# Sheet1.net
KiCad netlist of a schematic drawn in Altium Designer
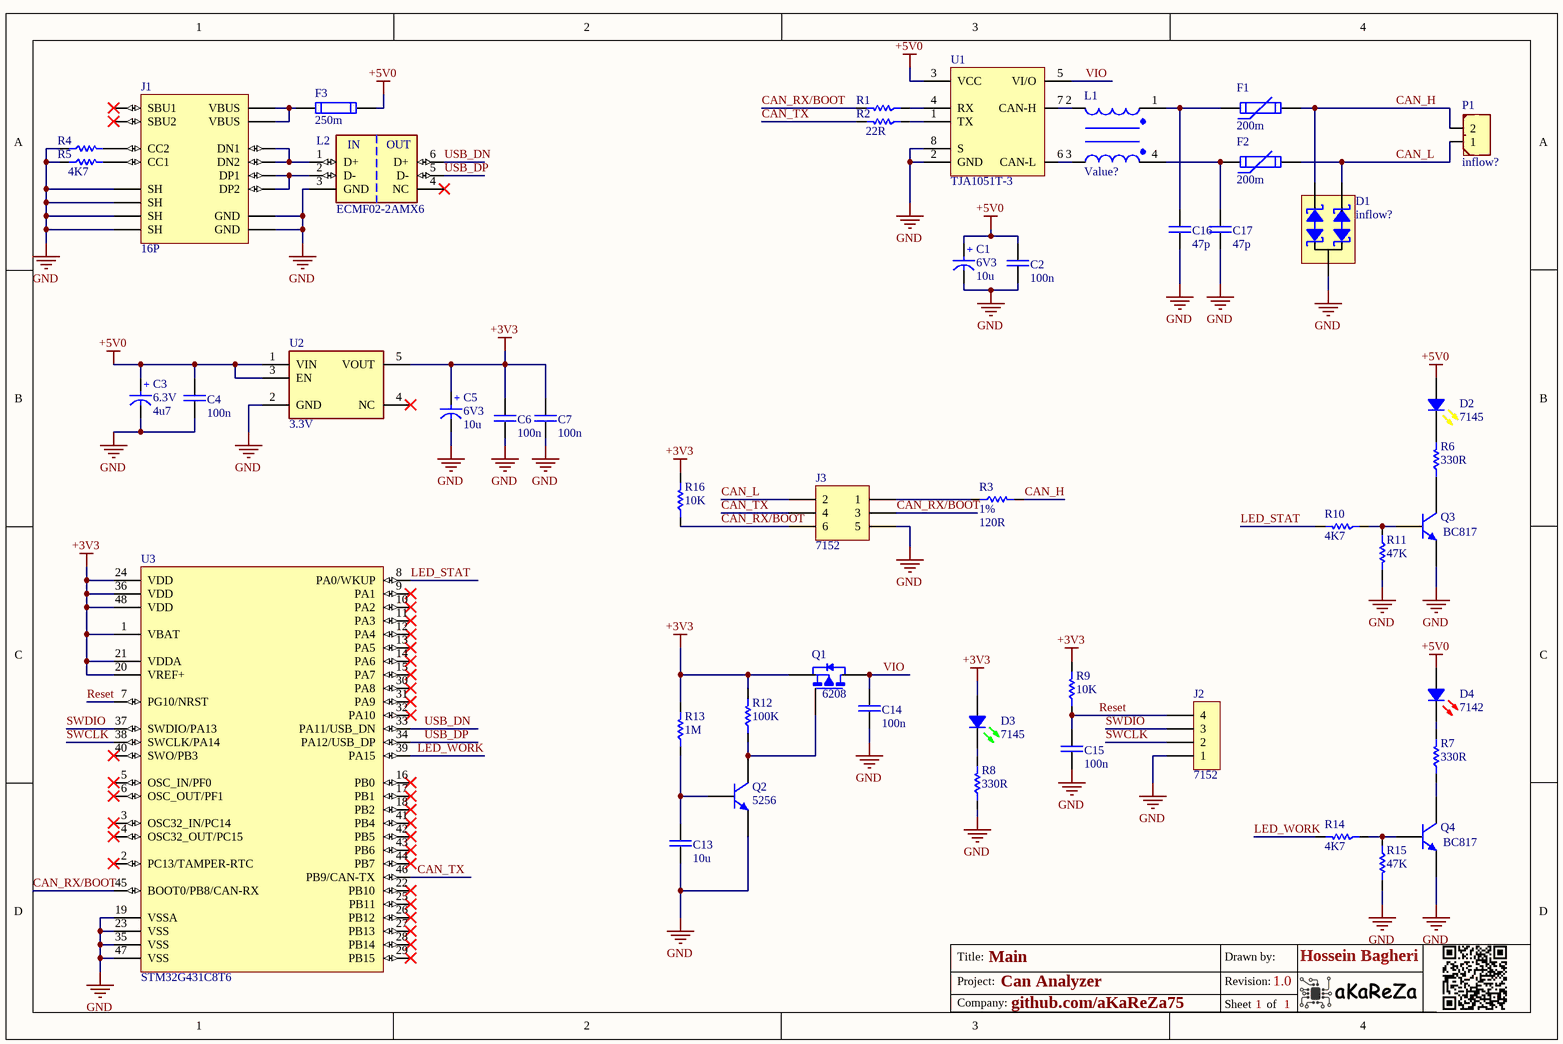
[diagram p0: Sheet1.SchDoc]

(export (version "E")
  (design (tool "Eeschema 10.0.6"))
  (components
    (comp (ref "C1")
      (value "10u")
      (footprint "SMT_C_Tantalum_A")
      (description "Tantalum Capacitor,TAJ Series-SMD")
      (fields (field (name "RATING") "6V3") (field (name "VALIDATION") "Valid"))
      (libsource (lib "aKaReZa") (part "Cap_Tantalum"))
    )
    (comp (ref "C2")
      (value "100n")
      (footprint "CAP 0805/2012")
      (description "Bipolar ceramic capacitor SMD")
      (fields (field (name "VALIDATION") "Valid"))
      (libsource (lib "aKaReZa") (part "Cap_Multi_SMD_100nF_0805"))
    )
    (comp (ref "C3")
      (value "4u7")
      (footprint "SMT_C_Tantalum_A")
      (description "Tantalum Capacitor,TAJ Series-SMD")
      (fields (field (name "RATING") "6.3V"))
      (libsource (lib "aKaReZa") (part "Cap_Tantalum"))
    )
    (comp (ref "C4")
      (value "100n")
      (footprint "CAP 0805/2012")
      (description "Bipolar ceramic capacitor SMD")
      (libsource (lib "aKaReZa") (part "Cap_Multi_SMD_100nF_0805"))
    )
    (comp (ref "C5")
      (value "10u")
      (footprint "SMT_C_Tantalum_B")
      (description "Tantalum Capacitor,TAJ Series-SMD")
      (fields (field (name "RATING") "6V3") (field (name "VALIDATION") "Valid"))
      (libsource (lib "aKaReZa") (part "Cap_Tantalum"))
    )
    (comp (ref "C6")
      (value "100n")
      (footprint "CAP 0805/2012")
      (description "Bipolar ceramic capacitor SMD")
      (fields (field (name "VALIDATION") "Valid"))
      (libsource (lib "aKaReZa") (part "Cap_Multi_SMD_100nF_0805"))
    )
    (comp (ref "C7")
      (value "100n")
      (footprint "CAP 0805/2012")
      (description "Bipolar ceramic capacitor SMD")
      (fields (field (name "VALIDATION") "Valid"))
      (libsource (lib "aKaReZa") (part "Cap_Multi_SMD_100nF_0805"))
    )
    (comp (ref "C13")
      (value "10u")
      (footprint "CAP 0805/2012")
      (description "Bipolar ceramic capacitor SMD")
      (fields (field (name "VALIDATION") "Valid"))
      (libsource (lib "aKaReZa") (part "Cap_Multi_SMD_0805"))
    )
    (comp (ref "C14")
      (value "100n")
      (footprint "CAP 0805/2012")
      (description "Bipolar ceramic capacitor SMD")
      (fields (field (name "VALIDATION") "Valid"))
      (libsource (lib "aKaReZa") (part "Cap_Multi_SMD_100nF_0805"))
    )
    (comp (ref "C15")
      (value "100n")
      (footprint "CAP 0805/2012")
      (description "Bipolar ceramic capacitor SMD")
      (fields (field (name "VALIDATION") "Valid"))
      (libsource (lib "aKaReZa") (part "Cap_Multi_SMD_100nF_0805"))
    )
    (comp (ref "C16")
      (value "47p")
      (footprint "CAP 0805/2012")
      (description "Bipolar ceramic capacitor SMD")
      (fields (field (name "VALIDATION") "Valid"))
      (libsource (lib "aKaReZa") (part "Cap_Multi_SMD_0805"))
    )
    (comp (ref "C17")
      (value "47p")
      (footprint "CAP 0805/2012")
      (description "Bipolar ceramic capacitor SMD")
      (fields (field (name "VALIDATION") "Valid"))
      (libsource (lib "aKaReZa") (part "Cap_Multi_SMD_0805"))
    )
    (comp (ref "D1")
      (value "SM712")
      (footprint "SOT23_M")
      (description "TVS, ESD PROTECT, 2CH, 400W/17A PP, 7.5VBR, ±8KV ESDmin")
      (fields (field (name "INFLOW") "inflow?") (field (name "VALIDATION") "Valid"))
      (libsource (lib "aKaReZa") (part "Semi_Diod_TVS_SM712"))
    )
    (comp (ref "D2")
      (value "Yellow")
      (footprint "LED-3mm_Yellow")
      (description "LED")
      (fields (field (name "INFLOW") "7145") (field (name "VALIDATION") "Valid"))
      (libsource (lib "aKaReZa") (part "Semi_LED_Yellow_3"))
    )
    (comp (ref "D3")
      (value "Green, 3'mm")
      (footprint "led-3mm")
      (description "LED")
      (fields (field (name "INFLOW") "7145") (field (name "VALIDATION") "Valid"))
      (libsource (lib "aKaReZa") (part "Semi_LED_Green_3"))
    )
    (comp (ref "D4")
      (value "Red, 3'mm")
      (footprint "LED-3mm(RED)")
      (description "LED")
      (fields (field (name "INFLOW") "7142") (field (name "VALIDATION") "Valid"))
      (libsource (lib "aKaReZa") (part "Semi_LED_Red_3"))
    )
    (comp (ref "F1")
      (value "200m")
      (footprint "1206_F")
      (description "SMD Resettable Fuses")
      (fields (field (name "VALIDATION") "Valid"))
      (libsource (lib "aKaReZa") (part "Other_Elec_PFUSE_SMD"))
    )
    (comp (ref "F2")
      (value "200m")
      (footprint "1206_F")
      (description "SMD Resettable Fuses")
      (fields (field (name "VALIDATION") "Valid"))
      (libsource (lib "aKaReZa") (part "Other_Elec_PFUSE_SMD"))
    )
    (comp (ref "F3")
      (value "250m")
      (footprint "1206_F")
      (description "Short circiut  protection")
      (libsource (lib "aKaReZa") (part "Other_Elec_Fuse_SMD"))
    )
    (comp (ref "J1")
      (value "16P")
      (footprint "USBC_SMD_16_USB4110 - Extended")
      (description "USB C Female Connector")
      (fields (field (name "VALIDATION") "NT"))
      (libsource (lib "aKaReZa") (part "Con_USB_C_16P"))
    )
    (comp (ref "J2")
      (value "4b")
      (footprint "HDR_THT_4M_2.54mm")
      (description "Header, single row, 4 pin")
      (fields (field (name "INFLOW") "7152") (field (name "VALIDATION") "NT"))
      (libsource (lib "aKaReZa") (part "Con_MPH_4x1_V_THT_2.54"))
    )
    (comp (ref "J3")
      (value "3x2")
      (footprint "HDR_THT_3x2M_2.54mm_RA")
      (description "Header, dual row, 6 pin")
      (fields (field (name "INFLOW") "7152") (field (name "VALIDATION") "NT"))
      (libsource (lib "aKaReZa") (part "Con_MPH_3x2_V_THT_2.54"))
    )
    (comp (ref "L1")
      (value "Value?")
      (footprint "FIL_DLW31SN900SQ2L_Extended")
      (description "2 Line Common Mode Choke Surface Mount 90 Ohms @ 100 MHz 370mA DCR 300mOhm")
      (fields (field (name "VALIDATION") "Valid"))
      (libsource (lib "aKaReZa") (part "Ind_EMI_DLW31SN900SQ2L"))
    )
    (comp (ref "L2")
      (value "ECMF02-2AMX6")
      (footprint "SON50P150X170X55-6N")
      (description "Common Mode Filter with ESD Protection for USB 2.0 and MIPI D-PHY/MDDI Interface")
      (fields (field (name "VALIDATION") "NT"))
      (libsource (lib "aKaReZa") (part "Ind_EMI_ECMF02-2AMX6"))
    )
    (comp (ref "P1")
      (value "2'Pin")
      (footprint "Phoenix_2PIN_RA_P5.08mm")
      (description "Power Connector 2'Pin")
      (fields (field (name "INFLOW") "inflow?") (field (name "VALIDATION") "NT"))
      (libsource (lib "aKaReZa") (part "Con_Power_2"))
    )
    (comp (ref "Q1")
      (value "P-Channel")
      (footprint "SOT23_N")
      (description "P-Channel MOSFET")
      (fields (field (name "INFLOW") "6208") (field (name "VALIDATION") "NT"))
      (libsource (lib "aKaReZa") (part "Semi_MOSFET_Si2301DS"))
    )
    (comp (ref "Q2")
      (value "NPN")
      (footprint "SOT23_N")
      (description "NPN General purpose Transistor")
      (fields (field (name "INFLOW") "5256") (field (name "VALIDATION") "Valid"))
      (libsource (lib "aKaReZa") (part "Semi_BJT_SS8050"))
    )
    (comp (ref "Q3")
      (value "BC817")
      (footprint "SOT23_N")
      (description "NPN General purpose Transistor")
      (fields (field (name "VALIDATION") "Valid"))
      (libsource (lib "aKaReZa") (part "Semi_BJT_BC817"))
    )
    (comp (ref "Q4")
      (value "BC817")
      (footprint "SOT23_N")
      (description "NPN General purpose Transistor")
      (fields (field (name "VALIDATION") "Valid"))
      (libsource (lib "aKaReZa") (part "Semi_BJT_BC817"))
    )
    (comp (ref "R1")
      (value "22R")
      (footprint "RES 0805 (2012X06L)")
      (description "Resistor")
      (fields (field (name "VALIDATION") "Valid"))
      (libsource (lib "aKaReZa") (part "Res_SMD_0805"))
    )
    (comp (ref "R2")
      (value "22R")
      (footprint "RES 0805 (2012X06L)")
      (description "Resistor")
      (fields (field (name "VALIDATION") "Valid"))
      (libsource (lib "aKaReZa") (part "Res_SMD_0805"))
    )
    (comp (ref "R3")
      (value "120R")
      (footprint "RES 0805 (2012X06L)")
      (description "Resistor")
      (fields (field (name "TYPE") "1%") (field (name "VALIDATION") "Valid"))
      (libsource (lib "aKaReZa") (part "Res_SMD_0805"))
    )
    (comp (ref "R4")
      (value "4K7")
      (footprint "RES 0805 (2012X06L)")
      (description "Resistor")
      (libsource (lib "aKaReZa") (part "Res_SMD_0805"))
    )
    (comp (ref "R5")
      (value "4K7")
      (footprint "RES 0805 (2012X06L)")
      (description "Resistor")
      (libsource (lib "aKaReZa") (part "Res_SMD_0805"))
    )
    (comp (ref "R6")
      (value "330R")
      (footprint "RES 0805 (2012X06L)")
      (description "Resistor")
      (fields (field (name "VALIDATION") "Valid"))
      (libsource (lib "aKaReZa") (part "Res_SMD_0805"))
    )
    (comp (ref "R7")
      (value "330R")
      (footprint "RES 0805 (2012X06L)")
      (description "Resistor")
      (fields (field (name "VALIDATION") "Valid"))
      (libsource (lib "aKaReZa") (part "Res_SMD_0805"))
    )
    (comp (ref "R8")
      (value "330R")
      (footprint "RES 0805 (2012X06L)")
      (description "Resistor")
      (fields (field (name "VALIDATION") "Valid"))
      (libsource (lib "aKaReZa") (part "Res_SMD_0805"))
    )
    (comp (ref "R9")
      (value "10K")
      (footprint "RES 0805 (2012X06L)")
      (description "Resistor")
      (fields (field (name "VALIDATION") "Valid"))
      (libsource (lib "aKaReZa") (part "Res_SMD_0805"))
    )
    (comp (ref "R10")
      (value "4K7")
      (footprint "RES 0805 (2012X06L)")
      (description "Resistor")
      (fields (field (name "VALIDATION") "Valid"))
      (libsource (lib "aKaReZa") (part "Res_SMD_0805"))
    )
    (comp (ref "R11")
      (value "47K")
      (footprint "RES 0805 (2012X06L)")
      (description "Resistor")
      (fields (field (name "VALIDATION") "Valid"))
      (libsource (lib "aKaReZa") (part "Res_SMD_0805"))
    )
    (comp (ref "R12")
      (value "100K")
      (footprint "RES 0805 (2012X06L)")
      (description "Resistor")
      (fields (field (name "VALIDATION") "Valid"))
      (libsource (lib "aKaReZa") (part "Res_SMD_0805"))
    )
    (comp (ref "R13")
      (value "1M")
      (footprint "RES 0805 (2012X06L)")
      (description "Resistor")
      (fields (field (name "VALIDATION") "Valid"))
      (libsource (lib "aKaReZa") (part "Res_SMD_0805"))
    )
    (comp (ref "R14")
      (value "4K7")
      (footprint "RES 0805 (2012X06L)")
      (description "Resistor")
      (fields (field (name "VALIDATION") "Valid"))
      (libsource (lib "aKaReZa") (part "Res_SMD_0805"))
    )
    (comp (ref "R15")
      (value "47K")
      (footprint "RES 0805 (2012X06L)")
      (description "Resistor")
      (fields (field (name "VALIDATION") "Valid"))
      (libsource (lib "aKaReZa") (part "Res_SMD_0805"))
    )
    (comp (ref "R16")
      (value "10K")
      (footprint "RES 0805 (2012X06L)")
      (description "Resistor")
      (fields (field (name "VALIDATION") "Valid"))
      (libsource (lib "aKaReZa") (part "Res_SMD_0805"))
    )
    (comp (ref "U1")
      (value "TJA1051T-3")
      (footprint "SO8_narrow_M")
      (fields (field (name "VALIDATION") "NT"))
      (libsource (lib "aKaReZa") (part "IC_Converter_TJA1051T-3"))
    )
    (comp (ref "U2")
      (value "3.3V")
      (footprint "SOT95P280X130-5N")
      (description "Fixed LDO Voltage Regulator 3.3V 300mA SOT-23-5")
      (fields (field (name "VALIDATION") "Valid"))
      (libsource (lib "aKaReZa") (part "IC_Reg_TLV74333PDBVR"))
    )
    (comp (ref "U3")
      (value "STM32G431C8T6")
      (footprint "LQFP48_N")
      (description "32-Bit mircrocontroller")
      (fields (field (name "VALIDATION") "NT"))
      (libsource (lib "aKaReZa") (part "IC_MCU_STM32G431C8T6"))
    )
  )
  (nets
    (net (code "1") (name "+3V3") (class "Default")
      (node (ref "C5") (pin "1") (pinfunction "+_1") (pintype "passive"))
      (node (ref "C6") (pin "1") (pinfunction "1_1") (pintype "passive"))
      (node (ref "C7") (pin "1") (pinfunction "1_1") (pintype "passive"))
      (node (ref "D3") (pin "1") (pinfunction "1_1") (pintype "passive"))
      (node (ref "Q1") (pin "2") (pinfunction "S_2") (pintype "passive"))
      (node (ref "R12") (pin "2") (pinfunction "2_2") (pintype "passive"))
      (node (ref "R13") (pin "2") (pinfunction "2_2") (pintype "passive"))
      (node (ref "R16") (pin "2") (pinfunction "2_2") (pintype "passive"))
      (node (ref "R9") (pin "2") (pinfunction "2_2") (pintype "passive"))
      (node (ref "U2") (pin "5") (pinfunction "VOUT_5") (pintype "passive"))
      (node (ref "U3") (pin "1") (pinfunction "VBAT_1") (pintype "power_in"))
      (node (ref "U3") (pin "20") (pinfunction "VREF+_20") (pintype "power_in"))
      (node (ref "U3") (pin "21") (pinfunction "VDDA_21") (pintype "power_in"))
      (node (ref "U3") (pin "24") (pinfunction "VDD_24") (pintype "power_in"))
      (node (ref "U3") (pin "36") (pinfunction "VDD_36") (pintype "power_in"))
      (node (ref "U3") (pin "48") (pinfunction "VDD_48") (pintype "power_in"))
    )
    (net (code "2") (name "+5V0") (class "Default")
      (node (ref "C1") (pin "1") (pinfunction "+_1") (pintype "passive"))
      (node (ref "C2") (pin "1") (pinfunction "1_1") (pintype "passive"))
      (node (ref "C3") (pin "1") (pinfunction "+_1") (pintype "passive"))
      (node (ref "C4") (pin "1") (pinfunction "1_1") (pintype "passive"))
      (node (ref "D2") (pin "1") (pinfunction "1_1") (pintype "passive"))
      (node (ref "D4") (pin "1") (pinfunction "1_1") (pintype "passive"))
      (node (ref "F3") (pin "2") (pinfunction "2_2") (pintype "passive"))
      (node (ref "U1") (pin "3") (pinfunction "VCC_3") (pintype "power_in"))
      (node (ref "U2") (pin "1") (pinfunction "VIN_1") (pintype "passive"))
      (node (ref "U2") (pin "3") (pinfunction "EN_3") (pintype "passive"))
    )
    (net (code "3") (name "/CAN_H") (class "Default")
      (node (ref "D1") (pin "1") (pinfunction "1_1") (pintype "passive"))
      (node (ref "F1") (pin "2") (pinfunction "2_2") (pintype "passive"))
      (node (ref "P1") (pin "2") (pinfunction "2_2") (pintype "passive"))
      (node (ref "R3") (pin "2") (pinfunction "2_2") (pintype "passive"))
    )
    (net (code "4") (name "/CAN_L") (class "Default")
      (node (ref "D1") (pin "2") (pinfunction "2_2") (pintype "passive"))
      (node (ref "F2") (pin "2") (pinfunction "2_2") (pintype "passive"))
      (node (ref "J3") (pin "2") (pinfunction "2_2") (pintype "passive"))
      (node (ref "P1") (pin "1") (pinfunction "1_1") (pintype "passive"))
    )
    (net (code "5") (name "/CAN_RX{slash}BOOT") (class "Default")
      (node (ref "J3") (pin "3") (pinfunction "3_3") (pintype "passive"))
      (node (ref "J3") (pin "6") (pinfunction "6_6") (pintype "passive"))
      (node (ref "R1") (pin "2") (pinfunction "2_2") (pintype "passive"))
      (node (ref "R16") (pin "1") (pinfunction "1_1") (pintype "passive"))
      (node (ref "U3") (pin "45") (pinfunction "BOOT0/PB8/CAN-RX_45") (pintype "bidirectional"))
    )
    (net (code "6") (name "/CAN_TX") (class "Default")
      (node (ref "J3") (pin "4") (pinfunction "4_4") (pintype "passive"))
      (node (ref "R2") (pin "2") (pinfunction "2_2") (pintype "passive"))
      (node (ref "U3") (pin "46") (pinfunction "PB9/CAN-TX_46") (pintype "bidirectional"))
    )
    (net (code "7") (name "/LED_STAT") (class "Default")
      (node (ref "R10") (pin "2") (pinfunction "2_2") (pintype "passive"))
      (node (ref "U3") (pin "8") (pinfunction "PA0/WKUP_8") (pintype "bidirectional"))
    )
    (net (code "8") (name "/LED_WORK") (class "Default")
      (node (ref "R14") (pin "2") (pinfunction "2_2") (pintype "passive"))
      (node (ref "U3") (pin "39") (pinfunction "PA15_39") (pintype "bidirectional"))
    )
    (net (code "9") (name "/Reset") (class "Default")
      (node (ref "C15") (pin "1") (pinfunction "1_1") (pintype "passive"))
      (node (ref "J2") (pin "4") (pinfunction "4_4") (pintype "passive"))
      (node (ref "R9") (pin "1") (pinfunction "1_1") (pintype "passive"))
      (node (ref "U3") (pin "7") (pinfunction "PG10/NRST_7") (pintype "bidirectional"))
    )
    (net (code "10") (name "/SWCLK") (class "Default")
      (node (ref "J2") (pin "2") (pinfunction "2_2") (pintype "passive"))
      (node (ref "U3") (pin "38") (pinfunction "SWCLK/PA14_38") (pintype "bidirectional"))
    )
    (net (code "11") (name "/SWDIO") (class "Default")
      (node (ref "J2") (pin "3") (pinfunction "3_3") (pintype "passive"))
      (node (ref "U3") (pin "37") (pinfunction "SWDIO/PA13_37") (pintype "bidirectional"))
    )
    (net (code "12") (name "/USB_DN") (class "Default")
      (node (ref "L2") (pin "6") (pinfunction "D+_6") (pintype "bidirectional"))
      (node (ref "U3") (pin "33") (pinfunction "PA11/USB_DN_33") (pintype "bidirectional"))
    )
    (net (code "13") (name "/USB_DP") (class "Default")
      (node (ref "L2") (pin "5") (pinfunction "D-_5") (pintype "bidirectional"))
      (node (ref "U3") (pin "34") (pinfunction "PA12/USB_DP_34") (pintype "bidirectional"))
    )
    (net (code "14") (name "/VIO") (class "Default")
      (node (ref "C14") (pin "1") (pinfunction "1_1") (pintype "passive"))
      (node (ref "Q1") (pin "3") (pinfunction "D_3") (pintype "passive"))
      (node (ref "U1") (pin "5") (pinfunction "VI/O_5") (pintype "passive"))
    )
    (net (code "15") (name "GND") (class "Default")
      (node (ref "C1") (pin "2") (pinfunction "-_2") (pintype "passive"))
      (node (ref "C13") (pin "2") (pinfunction "2_2") (pintype "passive"))
      (node (ref "C14") (pin "2") (pinfunction "2_2") (pintype "passive"))
      (node (ref "C15") (pin "2") (pinfunction "2_2") (pintype "passive"))
      (node (ref "C16") (pin "2") (pinfunction "2_2") (pintype "passive"))
      (node (ref "C17") (pin "2") (pinfunction "2_2") (pintype "passive"))
      (node (ref "C2") (pin "2") (pinfunction "2_2") (pintype "passive"))
      (node (ref "C3") (pin "2") (pinfunction "-_2") (pintype "passive"))
      (node (ref "C4") (pin "2") (pinfunction "2_2") (pintype "passive"))
      (node (ref "C5") (pin "2") (pinfunction "-_2") (pintype "passive"))
      (node (ref "C6") (pin "2") (pinfunction "2_2") (pintype "passive"))
      (node (ref "C7") (pin "2") (pinfunction "2_2") (pintype "passive"))
      (node (ref "D1") (pin "3") (pinfunction "3_3") (pintype "passive"))
      (node (ref "J1") (pin "A1B12") (pinfunction "GND_A1B12") (pintype "power_in"))
      (node (ref "J1") (pin "B1A12") (pinfunction "GND_B1A12") (pintype "power_in"))
      (node (ref "J1") (pin "S1") (pinfunction "SH_S1") (pintype "power_in"))
      (node (ref "J1") (pin "S2") (pinfunction "SH_S2") (pintype "power_in"))
      (node (ref "J1") (pin "S3") (pinfunction "SH_S3") (pintype "power_in"))
      (node (ref "J1") (pin "S4") (pinfunction "SH_S4") (pintype "power_in"))
      (node (ref "J2") (pin "1") (pinfunction "1_1") (pintype "passive"))
      (node (ref "J3") (pin "5") (pinfunction "5_5") (pintype "passive"))
      (node (ref "L2") (pin "3") (pinfunction "GND_3") (pintype "power_in"))
      (node (ref "Q2") (pin "2") (pinfunction "E_2") (pintype "passive"))
      (node (ref "Q3") (pin "2") (pinfunction "E_2") (pintype "passive"))
      (node (ref "Q4") (pin "2") (pinfunction "E_2") (pintype "passive"))
      (node (ref "R11") (pin "2") (pinfunction "2_2") (pintype "passive"))
      (node (ref "R15") (pin "2") (pinfunction "2_2") (pintype "passive"))
      (node (ref "R4") (pin "1") (pinfunction "1_1") (pintype "passive"))
      (node (ref "R5") (pin "1") (pinfunction "1_1") (pintype "passive"))
      (node (ref "R8") (pin "1") (pinfunction "1_1") (pintype "passive"))
      (node (ref "U1") (pin "2") (pinfunction "GND_2") (pintype "power_in"))
      (node (ref "U1") (pin "8") (pinfunction "S_8") (pintype "power_in"))
      (node (ref "U2") (pin "2") (pinfunction "GND_2") (pintype "passive"))
      (node (ref "U3") (pin "19") (pinfunction "VSSA_19") (pintype "power_in"))
      (node (ref "U3") (pin "23") (pinfunction "VSS_23") (pintype "power_in"))
      (node (ref "U3") (pin "35") (pinfunction "VSS_35") (pintype "power_in"))
      (node (ref "U3") (pin "47") (pinfunction "VSS_47") (pintype "power_in"))
    )
    (net (code "16") (name "Net-(C16-Pad1)") (class "Default")
      (node (ref "C16") (pin "1") (pinfunction "1_1") (pintype "passive"))
      (node (ref "F1") (pin "1") (pinfunction "1_1") (pintype "passive"))
      (node (ref "L1") (pin "1") (pinfunction "1_1") (pintype "passive"))
    )
    (net (code "17") (name "Net-(C17-Pad1)") (class "Default")
      (node (ref "C17") (pin "1") (pinfunction "1_1") (pintype "passive"))
      (node (ref "F2") (pin "1") (pinfunction "1_1") (pintype "passive"))
      (node (ref "L1") (pin "4") (pinfunction "4_4") (pintype "passive"))
    )
    (net (code "18") (name "Net-(D2-Pad2)") (class "Default")
      (node (ref "D2") (pin "2") (pinfunction "2_2") (pintype "passive"))
      (node (ref "R6") (pin "2") (pinfunction "2_2") (pintype "passive"))
    )
    (net (code "19") (name "Net-(D3-Pad2)") (class "Default")
      (node (ref "D3") (pin "2") (pinfunction "2_2") (pintype "passive"))
      (node (ref "R8") (pin "2") (pinfunction "2_2") (pintype "passive"))
    )
    (net (code "20") (name "Net-(D4-Pad2)") (class "Default")
      (node (ref "D4") (pin "2") (pinfunction "2_2") (pintype "passive"))
      (node (ref "R7") (pin "2") (pinfunction "2_2") (pintype "passive"))
    )
    (net (code "21") (name "Net-(F3-Pad1)") (class "Default")
      (node (ref "F3") (pin "1") (pinfunction "1_1") (pintype "passive"))
      (node (ref "J1") (pin "A4B9") (pinfunction "VBUS_A4B9") (pintype "power_in"))
      (node (ref "J1") (pin "B4A9") (pinfunction "VBUS_B4A9") (pintype "power_in"))
    )
    (net (code "22") (name "Net-(J1-CC1)") (class "Default")
      (node (ref "J1") (pin "A5") (pinfunction "CC1_A5") (pintype "bidirectional"))
      (node (ref "R4") (pin "2") (pinfunction "2_2") (pintype "passive"))
    )
    (net (code "23") (name "Net-(J1-CC2)") (class "Default")
      (node (ref "J1") (pin "B5") (pinfunction "CC2_B5") (pintype "bidirectional"))
      (node (ref "R5") (pin "2") (pinfunction "2_2") (pintype "passive"))
    )
    (net (code "24") (name "Net-(J1-DN1)") (class "Default")
      (node (ref "J1") (pin "A7") (pinfunction "DN1_A7") (pintype "bidirectional"))
      (node (ref "J1") (pin "B7") (pinfunction "DN2_B7") (pintype "bidirectional"))
      (node (ref "L2") (pin "1") (pinfunction "D+_1") (pintype "bidirectional"))
    )
    (net (code "25") (name "Net-(J1-DP1)") (class "Default")
      (node (ref "J1") (pin "A6") (pinfunction "DP1_A6") (pintype "bidirectional"))
      (node (ref "J1") (pin "B6") (pinfunction "DP2_B6") (pintype "bidirectional"))
      (node (ref "L2") (pin "2") (pinfunction "D-_2") (pintype "bidirectional"))
    )
    (net (code "26") (name "Net-(J3-Pad1)") (class "Default")
      (node (ref "J3") (pin "1") (pinfunction "1_1") (pintype "passive"))
      (node (ref "R3") (pin "1") (pinfunction "1_1") (pintype "passive"))
    )
    (net (code "27") (name "Net-(Q1-G)") (class "Default")
      (node (ref "Q1") (pin "1") (pinfunction "G_1") (pintype "passive"))
      (node (ref "Q2") (pin "3") (pinfunction "C_3") (pintype "passive"))
      (node (ref "R12") (pin "1") (pinfunction "1_1") (pintype "passive"))
    )
    (net (code "28") (name "Net-(Q2-B)") (class "Default")
      (node (ref "C13") (pin "1") (pinfunction "1_1") (pintype "passive"))
      (node (ref "Q2") (pin "1") (pinfunction "B_1") (pintype "passive"))
      (node (ref "R13") (pin "1") (pinfunction "1_1") (pintype "passive"))
    )
    (net (code "29") (name "Net-(Q3-B)") (class "Default")
      (node (ref "Q3") (pin "1") (pinfunction "B_1") (pintype "passive"))
      (node (ref "R10") (pin "1") (pinfunction "1_1") (pintype "passive"))
      (node (ref "R11") (pin "1") (pinfunction "1_1") (pintype "passive"))
    )
    (net (code "30") (name "Net-(Q3-C)") (class "Default")
      (node (ref "Q3") (pin "3") (pinfunction "C_3") (pintype "passive"))
      (node (ref "R6") (pin "1") (pinfunction "1_1") (pintype "passive"))
    )
    (net (code "31") (name "Net-(Q4-B)") (class "Default")
      (node (ref "Q4") (pin "1") (pinfunction "B_1") (pintype "passive"))
      (node (ref "R14") (pin "1") (pinfunction "1_1") (pintype "passive"))
      (node (ref "R15") (pin "1") (pinfunction "1_1") (pintype "passive"))
    )
    (net (code "32") (name "Net-(Q4-C)") (class "Default")
      (node (ref "Q4") (pin "3") (pinfunction "C_3") (pintype "passive"))
      (node (ref "R7") (pin "1") (pinfunction "1_1") (pintype "passive"))
    )
    (net (code "33") (name "Net-(U1-CAN-H)") (class "Default")
      (node (ref "L1") (pin "2") (pinfunction "2_2") (pintype "passive"))
      (node (ref "U1") (pin "7") (pinfunction "CAN-H_7") (pintype "passive"))
    )
    (net (code "34") (name "Net-(U1-CAN-L)") (class "Default")
      (node (ref "L1") (pin "3") (pinfunction "3_3") (pintype "passive"))
      (node (ref "U1") (pin "6") (pinfunction "CAN-L_6") (pintype "passive"))
    )
    (net (code "35") (name "Net-(U1-RX)") (class "Default")
      (node (ref "R1") (pin "1") (pinfunction "1_1") (pintype "passive"))
      (node (ref "U1") (pin "4") (pinfunction "RX_4") (pintype "open_collector"))
    )
    (net (code "36") (name "Net-(U1-TX)") (class "Default")
      (node (ref "R2") (pin "1") (pinfunction "1_1") (pintype "passive"))
      (node (ref "U1") (pin "1") (pinfunction "TX_1") (pintype "open_collector"))
    )
    (net (code "37") (name "unconnected-(J1-SBU1-PadA8)") (class "Default")
      (node (ref "J1") (pin "A8") (pinfunction "SBU1_A8") (pintype "bidirectional+no_connect"))
    )
    (net (code "38") (name "unconnected-(J1-SBU2-PadB8)") (class "Default")
      (node (ref "J1") (pin "B8") (pinfunction "SBU2_B8") (pintype "bidirectional+no_connect"))
    )
    (net (code "39") (name "unconnected-(L2-NC-Pad4)") (class "Default")
      (node (ref "L2") (pin "4") (pinfunction "NC_4") (pintype "passive+no_connect"))
    )
    (net (code "40") (name "unconnected-(U2-NC-Pad4)") (class "Default")
      (node (ref "U2") (pin "4") (pinfunction "NC_4") (pintype "passive+no_connect"))
    )
    (net (code "41") (name "unconnected-(U3-OSC32_IN{slash}PC14-Pad3)") (class "Default")
      (node (ref "U3") (pin "3") (pinfunction "OSC32_IN/PC14_3") (pintype "bidirectional+no_connect"))
    )
    (net (code "42") (name "unconnected-(U3-OSC32_OUT{slash}PC15-Pad4)") (class "Default")
      (node (ref "U3") (pin "4") (pinfunction "OSC32_OUT/PC15_4") (pintype "bidirectional+no_connect"))
    )
    (net (code "43") (name "unconnected-(U3-OSC_IN{slash}PF0-Pad5)") (class "Default")
      (node (ref "U3") (pin "5") (pinfunction "OSC_IN/PF0_5") (pintype "bidirectional+no_connect"))
    )
    (net (code "44") (name "unconnected-(U3-OSC_OUT{slash}PF1-Pad6)") (class "Default")
      (node (ref "U3") (pin "6") (pinfunction "OSC_OUT/PF1_6") (pintype "bidirectional+no_connect"))
    )
    (net (code "45") (name "unconnected-(U3-PA1-Pad9)") (class "Default")
      (node (ref "U3") (pin "9") (pinfunction "PA1_9") (pintype "bidirectional+no_connect"))
    )
    (net (code "46") (name "unconnected-(U3-PA2-Pad10)") (class "Default")
      (node (ref "U3") (pin "10") (pinfunction "PA2_10") (pintype "bidirectional+no_connect"))
    )
    (net (code "47") (name "unconnected-(U3-PA3-Pad11)") (class "Default")
      (node (ref "U3") (pin "11") (pinfunction "PA3_11") (pintype "bidirectional+no_connect"))
    )
    (net (code "48") (name "unconnected-(U3-PA4-Pad12)") (class "Default")
      (node (ref "U3") (pin "12") (pinfunction "PA4_12") (pintype "bidirectional+no_connect"))
    )
    (net (code "49") (name "unconnected-(U3-PA5-Pad13)") (class "Default")
      (node (ref "U3") (pin "13") (pinfunction "PA5_13") (pintype "bidirectional+no_connect"))
    )
    (net (code "50") (name "unconnected-(U3-PA6-Pad14)") (class "Default")
      (node (ref "U3") (pin "14") (pinfunction "PA6_14") (pintype "bidirectional+no_connect"))
    )
    (net (code "51") (name "unconnected-(U3-PA7-Pad15)") (class "Default")
      (node (ref "U3") (pin "15") (pinfunction "PA7_15") (pintype "bidirectional+no_connect"))
    )
    (net (code "52") (name "unconnected-(U3-PA8-Pad30)") (class "Default")
      (node (ref "U3") (pin "30") (pinfunction "PA8_30") (pintype "bidirectional+no_connect"))
    )
    (net (code "53") (name "unconnected-(U3-PA9-Pad31)") (class "Default")
      (node (ref "U3") (pin "31") (pinfunction "PA9_31") (pintype "bidirectional+no_connect"))
    )
    (net (code "54") (name "unconnected-(U3-PA10-Pad32)") (class "Default")
      (node (ref "U3") (pin "32") (pinfunction "PA10_32") (pintype "bidirectional+no_connect"))
    )
    (net (code "55") (name "unconnected-(U3-PB0-Pad16)") (class "Default")
      (node (ref "U3") (pin "16") (pinfunction "PB0_16") (pintype "bidirectional+no_connect"))
    )
    (net (code "56") (name "unconnected-(U3-PB1-Pad17)") (class "Default")
      (node (ref "U3") (pin "17") (pinfunction "PB1_17") (pintype "bidirectional+no_connect"))
    )
    (net (code "57") (name "unconnected-(U3-PB2-Pad18)") (class "Default")
      (node (ref "U3") (pin "18") (pinfunction "PB2_18") (pintype "bidirectional+no_connect"))
    )
    (net (code "58") (name "unconnected-(U3-PB4-Pad41)") (class "Default")
      (node (ref "U3") (pin "41") (pinfunction "PB4_41") (pintype "bidirectional+no_connect"))
    )
    (net (code "59") (name "unconnected-(U3-PB5-Pad42)") (class "Default")
      (node (ref "U3") (pin "42") (pinfunction "PB5_42") (pintype "bidirectional+no_connect"))
    )
    (net (code "60") (name "unconnected-(U3-PB6-Pad43)") (class "Default")
      (node (ref "U3") (pin "43") (pinfunction "PB6_43") (pintype "bidirectional+no_connect"))
    )
    (net (code "61") (name "unconnected-(U3-PB7-Pad44)") (class "Default")
      (node (ref "U3") (pin "44") (pinfunction "PB7_44") (pintype "bidirectional+no_connect"))
    )
    (net (code "62") (name "unconnected-(U3-PB10-Pad22)") (class "Default")
      (node (ref "U3") (pin "22") (pinfunction "PB10_22") (pintype "bidirectional+no_connect"))
    )
    (net (code "63") (name "unconnected-(U3-PB11-Pad25)") (class "Default")
      (node (ref "U3") (pin "25") (pinfunction "PB11_25") (pintype "bidirectional+no_connect"))
    )
    (net (code "64") (name "unconnected-(U3-PB12-Pad26)") (class "Default")
      (node (ref "U3") (pin "26") (pinfunction "PB12_26") (pintype "bidirectional+no_connect"))
    )
    (net (code "65") (name "unconnected-(U3-PB13-Pad27)") (class "Default")
      (node (ref "U3") (pin "27") (pinfunction "PB13_27") (pintype "bidirectional+no_connect"))
    )
    (net (code "66") (name "unconnected-(U3-PB14-Pad28)") (class "Default")
      (node (ref "U3") (pin "28") (pinfunction "PB14_28") (pintype "bidirectional+no_connect"))
    )
    (net (code "67") (name "unconnected-(U3-PB15-Pad29)") (class "Default")
      (node (ref "U3") (pin "29") (pinfunction "PB15_29") (pintype "bidirectional+no_connect"))
    )
    (net (code "68") (name "unconnected-(U3-PC13{slash}TAMPER-RTC-Pad2)") (class "Default")
      (node (ref "U3") (pin "2") (pinfunction "PC13/TAMPER-RTC_2") (pintype "bidirectional+no_connect"))
    )
    (net (code "69") (name "unconnected-(U3-SWO{slash}PB3-Pad40)") (class "Default")
      (node (ref "U3") (pin "40") (pinfunction "SWO/PB3_40") (pintype "bidirectional+no_connect"))
    )
  )
)
